# 3DM.net
KiCad netlist of a schematic drawn in EAGLE
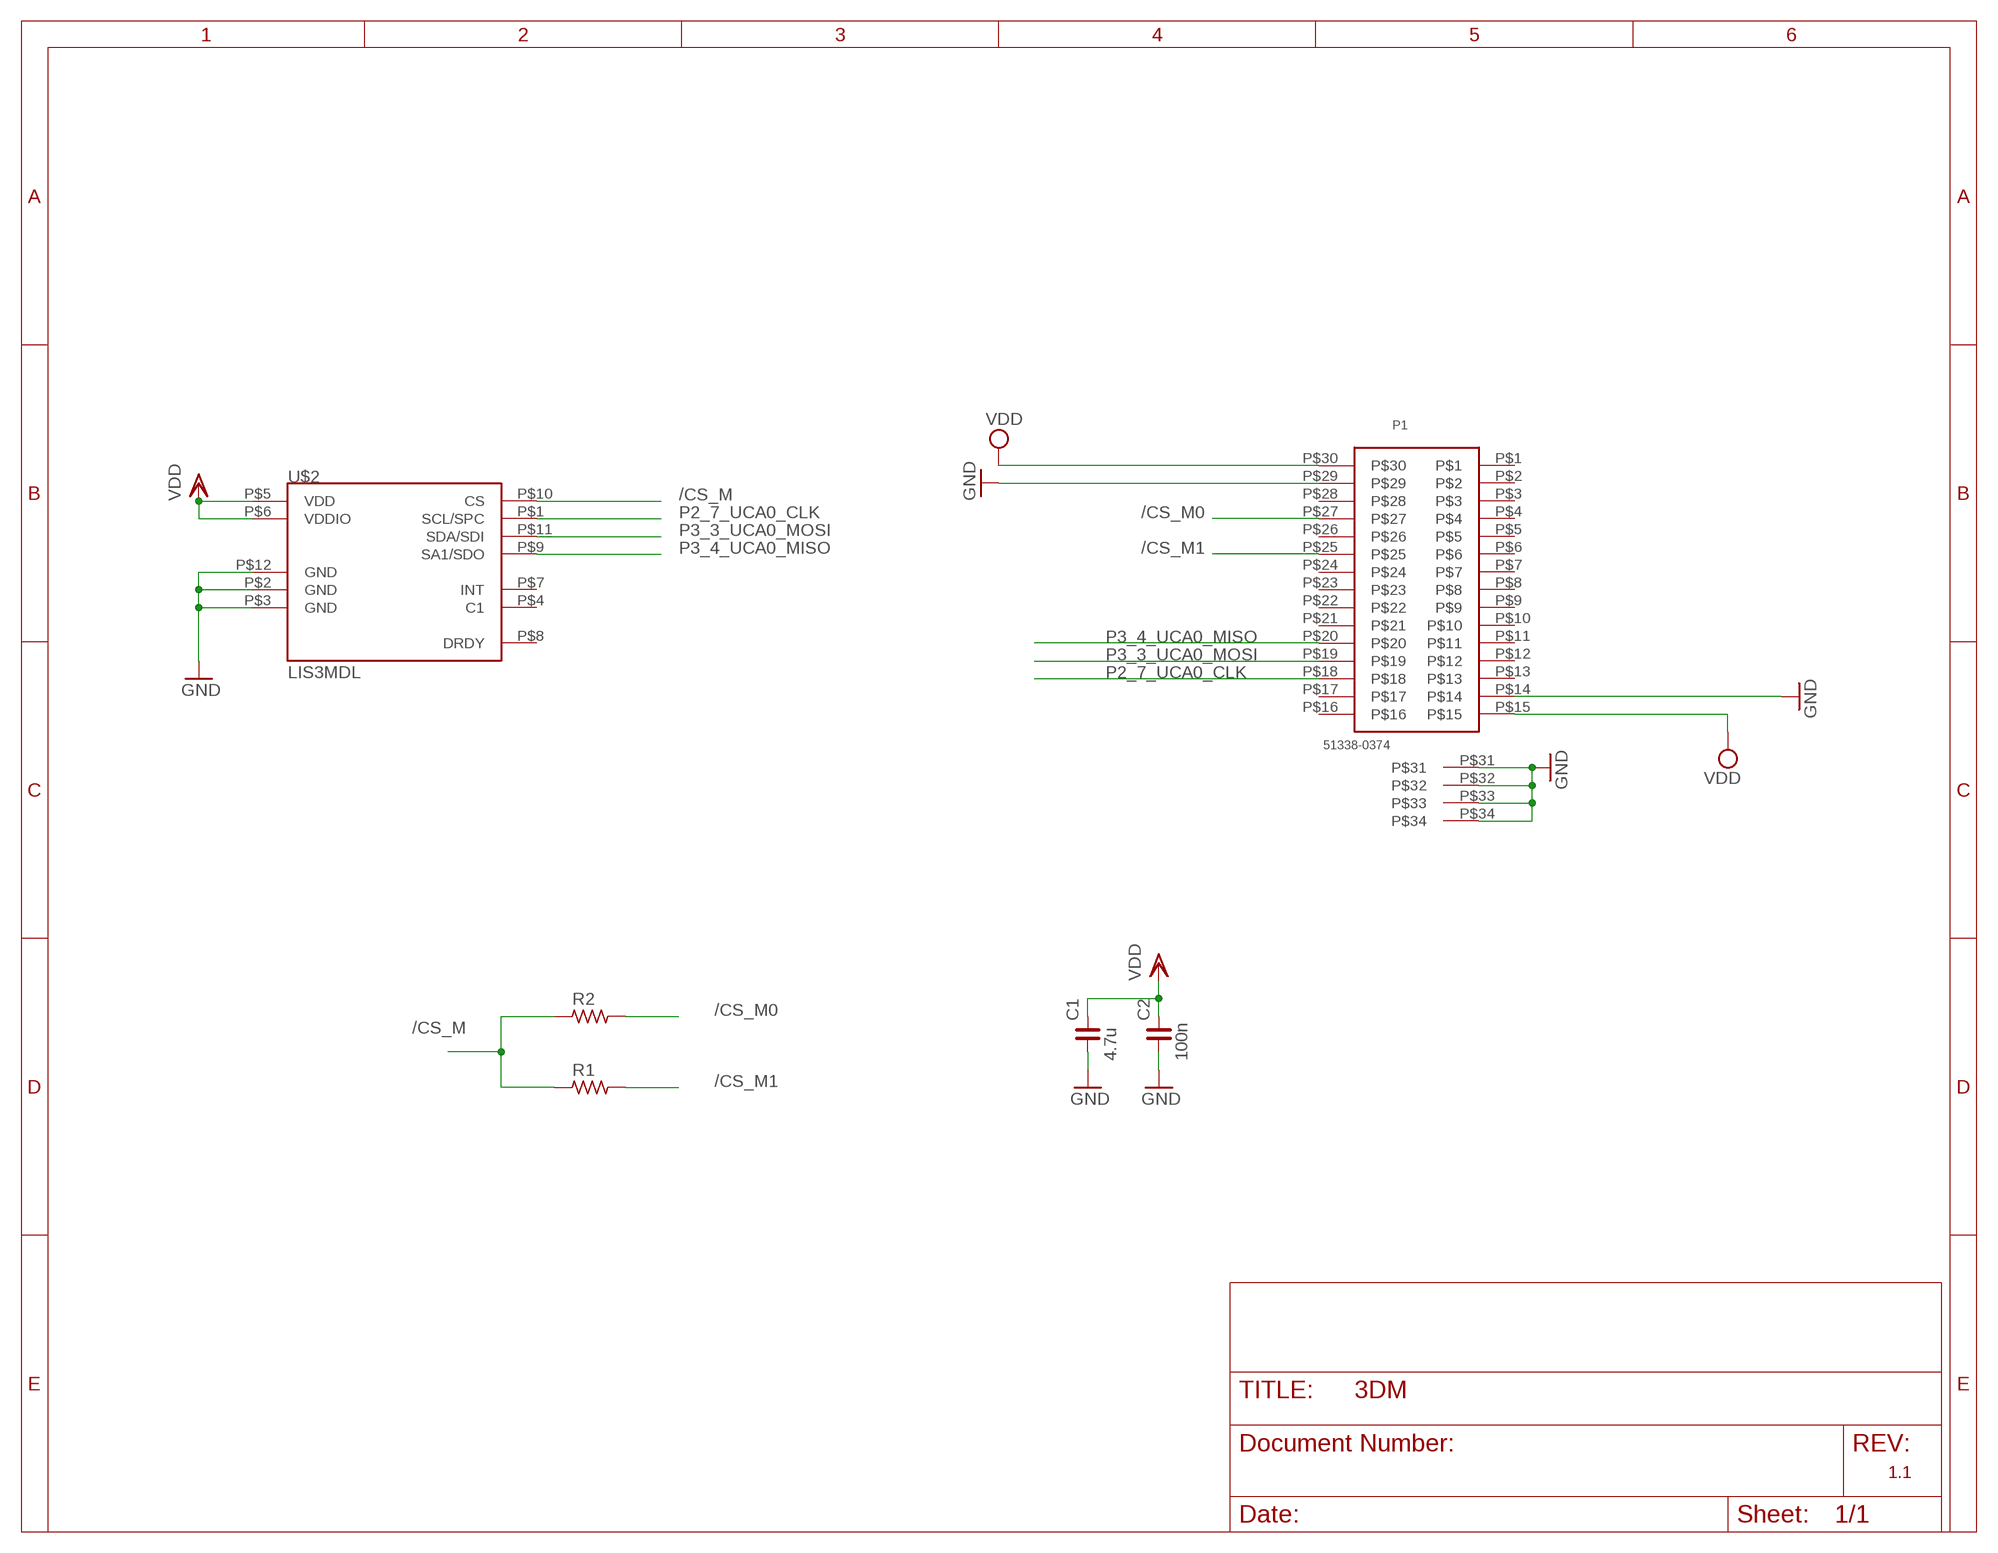
[diagram p0: schematic, sheet 1]

(export (version "E")
  (design (tool "Eeschema 10.0.6"))
  (components
    (comp (ref "C1")
      (value "4.7u")
      (footprint "eagle-import:C0402")
      (libsource (lib "eagle-import") (part "C_0402"))
    )
    (comp (ref "C2")
      (value "100n")
      (footprint "eagle-import:C0402")
      (libsource (lib "eagle-import") (part "C_0402"))
    )
    (comp (ref "P1")
      (value "51338-0374")
      (footprint "eagle-import:51338-0374_RECEPTACLE")
      (libsource (lib "eagle-import") (part "51338-0374_RECEPTACLE"))
    )
    (comp (ref "R1")
      (value "R_0402")
      (footprint "eagle-import:R0402")
      (libsource (lib "eagle-import") (part "R_0402"))
    )
    (comp (ref "R2")
      (value "R_0402")
      (footprint "eagle-import:R0402")
      (libsource (lib "eagle-import") (part "R_0402"))
    )
    (comp (ref "U$2")
      (value "LIS3MDL")
      (footprint "eagle-import:VFLGA-2X2X1")
      (libsource (lib "eagle-import") (part "LIS3MDL"))
    )
  )
  (nets
    (net (code "1") (name "/P2_7_UCA0_CLK") (class "Default")
      (node (ref "P1") (pin "P$18") (pinfunction "P$18_P$18") (pintype "bidirectional"))
      (node (ref "U$2") (pin "P$1") (pinfunction "SCL/SPC_P$1") (pintype "bidirectional"))
    )
    (net (code "2") (name "/P3_3_UCA0_MOSI") (class "Default")
      (node (ref "P1") (pin "P$19") (pinfunction "P$19_P$19") (pintype "bidirectional"))
      (node (ref "U$2") (pin "P$11") (pinfunction "SDA/SDI_P$11") (pintype "bidirectional"))
    )
    (net (code "3") (name "/P3_4_UCA0_MISO") (class "Default")
      (node (ref "P1") (pin "P$20") (pinfunction "P$20_P$20") (pintype "bidirectional"))
      (node (ref "U$2") (pin "P$9") (pinfunction "SA1/SDO_P$9") (pintype "bidirectional"))
    )
    (net (code "4") (name "/{slash}CS_M") (class "Default")
      (node (ref "R1") (pin "1") (pinfunction "1_1") (pintype "passive"))
      (node (ref "R2") (pin "1") (pinfunction "1_1") (pintype "passive"))
      (node (ref "U$2") (pin "P$10") (pinfunction "CS_P$10") (pintype "bidirectional"))
    )
    (net (code "5") (name "/{slash}CS_M0") (class "Default")
      (node (ref "P1") (pin "P$27") (pinfunction "P$27_P$27") (pintype "bidirectional"))
      (node (ref "R2") (pin "2") (pinfunction "2_2") (pintype "passive"))
    )
    (net (code "6") (name "/{slash}CS_M1") (class "Default")
      (node (ref "P1") (pin "P$25") (pinfunction "P$25_P$25") (pintype "bidirectional"))
      (node (ref "R1") (pin "2") (pinfunction "2_2") (pintype "passive"))
    )
    (net (code "7") (name "GND") (class "Default")
      (node (ref "C1") (pin "1") (pinfunction "1_1") (pintype "passive"))
      (node (ref "C2") (pin "1") (pinfunction "1_1") (pintype "passive"))
      (node (ref "P1") (pin "P$14") (pinfunction "P$14_P$14") (pintype "bidirectional"))
      (node (ref "P1") (pin "P$29") (pinfunction "P$29_P$29") (pintype "bidirectional"))
      (node (ref "P1") (pin "P$31") (pinfunction "P$31_P$31") (pintype "bidirectional"))
      (node (ref "P1") (pin "P$32") (pinfunction "P$32_P$32") (pintype "bidirectional"))
      (node (ref "P1") (pin "P$33") (pinfunction "P$33_P$33") (pintype "bidirectional"))
      (node (ref "P1") (pin "P$34") (pinfunction "P$34_P$34") (pintype "bidirectional"))
      (node (ref "U$2") (pin "P$12") (pinfunction "GND_P$12") (pintype "bidirectional"))
      (node (ref "U$2") (pin "P$2") (pinfunction "GND_P$2") (pintype "bidirectional"))
      (node (ref "U$2") (pin "P$3") (pinfunction "GND_P$3") (pintype "bidirectional"))
    )
    (net (code "8") (name "VDD") (class "Default")
      (node (ref "C1") (pin "2") (pinfunction "2_2") (pintype "passive"))
      (node (ref "C2") (pin "2") (pinfunction "2_2") (pintype "passive"))
      (node (ref "P1") (pin "P$15") (pinfunction "P$15_P$15") (pintype "bidirectional"))
      (node (ref "P1") (pin "P$30") (pinfunction "P$30_P$30") (pintype "bidirectional"))
      (node (ref "U$2") (pin "P$5") (pinfunction "VDD_P$5") (pintype "bidirectional"))
      (node (ref "U$2") (pin "P$6") (pinfunction "VDDIO_P$6") (pintype "bidirectional"))
    )
    (net (code "9") (name "unconnected-(P1-PadP$1)") (class "Default")
      (node (ref "P1") (pin "P$1") (pinfunction "P$1_P$1") (pintype "bidirectional"))
    )
    (net (code "10") (name "unconnected-(P1-PadP$2)") (class "Default")
      (node (ref "P1") (pin "P$2") (pinfunction "P$2_P$2") (pintype "bidirectional"))
    )
    (net (code "11") (name "unconnected-(P1-PadP$3)") (class "Default")
      (node (ref "P1") (pin "P$3") (pinfunction "P$3_P$3") (pintype "bidirectional"))
    )
    (net (code "12") (name "unconnected-(P1-PadP$4)") (class "Default")
      (node (ref "P1") (pin "P$4") (pinfunction "P$4_P$4") (pintype "bidirectional"))
    )
    (net (code "13") (name "unconnected-(P1-PadP$5)") (class "Default")
      (node (ref "P1") (pin "P$5") (pinfunction "P$5_P$5") (pintype "bidirectional"))
    )
    (net (code "14") (name "unconnected-(P1-PadP$6)") (class "Default")
      (node (ref "P1") (pin "P$6") (pinfunction "P$6_P$6") (pintype "bidirectional"))
    )
    (net (code "15") (name "unconnected-(P1-PadP$7)") (class "Default")
      (node (ref "P1") (pin "P$7") (pinfunction "P$7_P$7") (pintype "bidirectional"))
    )
    (net (code "16") (name "unconnected-(P1-PadP$8)") (class "Default")
      (node (ref "P1") (pin "P$8") (pinfunction "P$8_P$8") (pintype "bidirectional"))
    )
    (net (code "17") (name "unconnected-(P1-PadP$9)") (class "Default")
      (node (ref "P1") (pin "P$9") (pinfunction "P$9_P$9") (pintype "bidirectional"))
    )
    (net (code "18") (name "unconnected-(P1-PadP$10)") (class "Default")
      (node (ref "P1") (pin "P$10") (pinfunction "P$10_P$10") (pintype "bidirectional"))
    )
    (net (code "19") (name "unconnected-(P1-PadP$11)") (class "Default")
      (node (ref "P1") (pin "P$11") (pinfunction "P$11_P$11") (pintype "bidirectional"))
    )
    (net (code "20") (name "unconnected-(P1-PadP$12)") (class "Default")
      (node (ref "P1") (pin "P$12") (pinfunction "P$12_P$12") (pintype "bidirectional"))
    )
    (net (code "21") (name "unconnected-(P1-PadP$13)") (class "Default")
      (node (ref "P1") (pin "P$13") (pinfunction "P$13_P$13") (pintype "bidirectional"))
    )
    (net (code "22") (name "unconnected-(P1-PadP$16)") (class "Default")
      (node (ref "P1") (pin "P$16") (pinfunction "P$16_P$16") (pintype "bidirectional"))
    )
    (net (code "23") (name "unconnected-(P1-PadP$17)") (class "Default")
      (node (ref "P1") (pin "P$17") (pinfunction "P$17_P$17") (pintype "bidirectional"))
    )
    (net (code "24") (name "unconnected-(P1-PadP$21)") (class "Default")
      (node (ref "P1") (pin "P$21") (pinfunction "P$21_P$21") (pintype "bidirectional"))
    )
    (net (code "25") (name "unconnected-(P1-PadP$22)") (class "Default")
      (node (ref "P1") (pin "P$22") (pinfunction "P$22_P$22") (pintype "bidirectional"))
    )
    (net (code "26") (name "unconnected-(P1-PadP$23)") (class "Default")
      (node (ref "P1") (pin "P$23") (pinfunction "P$23_P$23") (pintype "bidirectional"))
    )
    (net (code "27") (name "unconnected-(P1-PadP$24)") (class "Default")
      (node (ref "P1") (pin "P$24") (pinfunction "P$24_P$24") (pintype "bidirectional"))
    )
    (net (code "28") (name "unconnected-(P1-PadP$26)") (class "Default")
      (node (ref "P1") (pin "P$26") (pinfunction "P$26_P$26") (pintype "bidirectional"))
    )
    (net (code "29") (name "unconnected-(P1-PadP$28)") (class "Default")
      (node (ref "P1") (pin "P$28") (pinfunction "P$28_P$28") (pintype "bidirectional"))
    )
    (net (code "30") (name "unconnected-(U$2-C1-PadP$4)") (class "Default")
      (node (ref "U$2") (pin "P$4") (pinfunction "C1_P$4") (pintype "bidirectional"))
    )
    (net (code "31") (name "unconnected-(U$2-DRDY-PadP$8)") (class "Default")
      (node (ref "U$2") (pin "P$8") (pinfunction "DRDY_P$8") (pintype "bidirectional"))
    )
    (net (code "32") (name "unconnected-(U$2-INT-PadP$7)") (class "Default")
      (node (ref "U$2") (pin "P$7") (pinfunction "INT_P$7") (pintype "bidirectional"))
    )
  )
)
